# ps.net
KiCad netlist of a schematic drawn in EAGLE
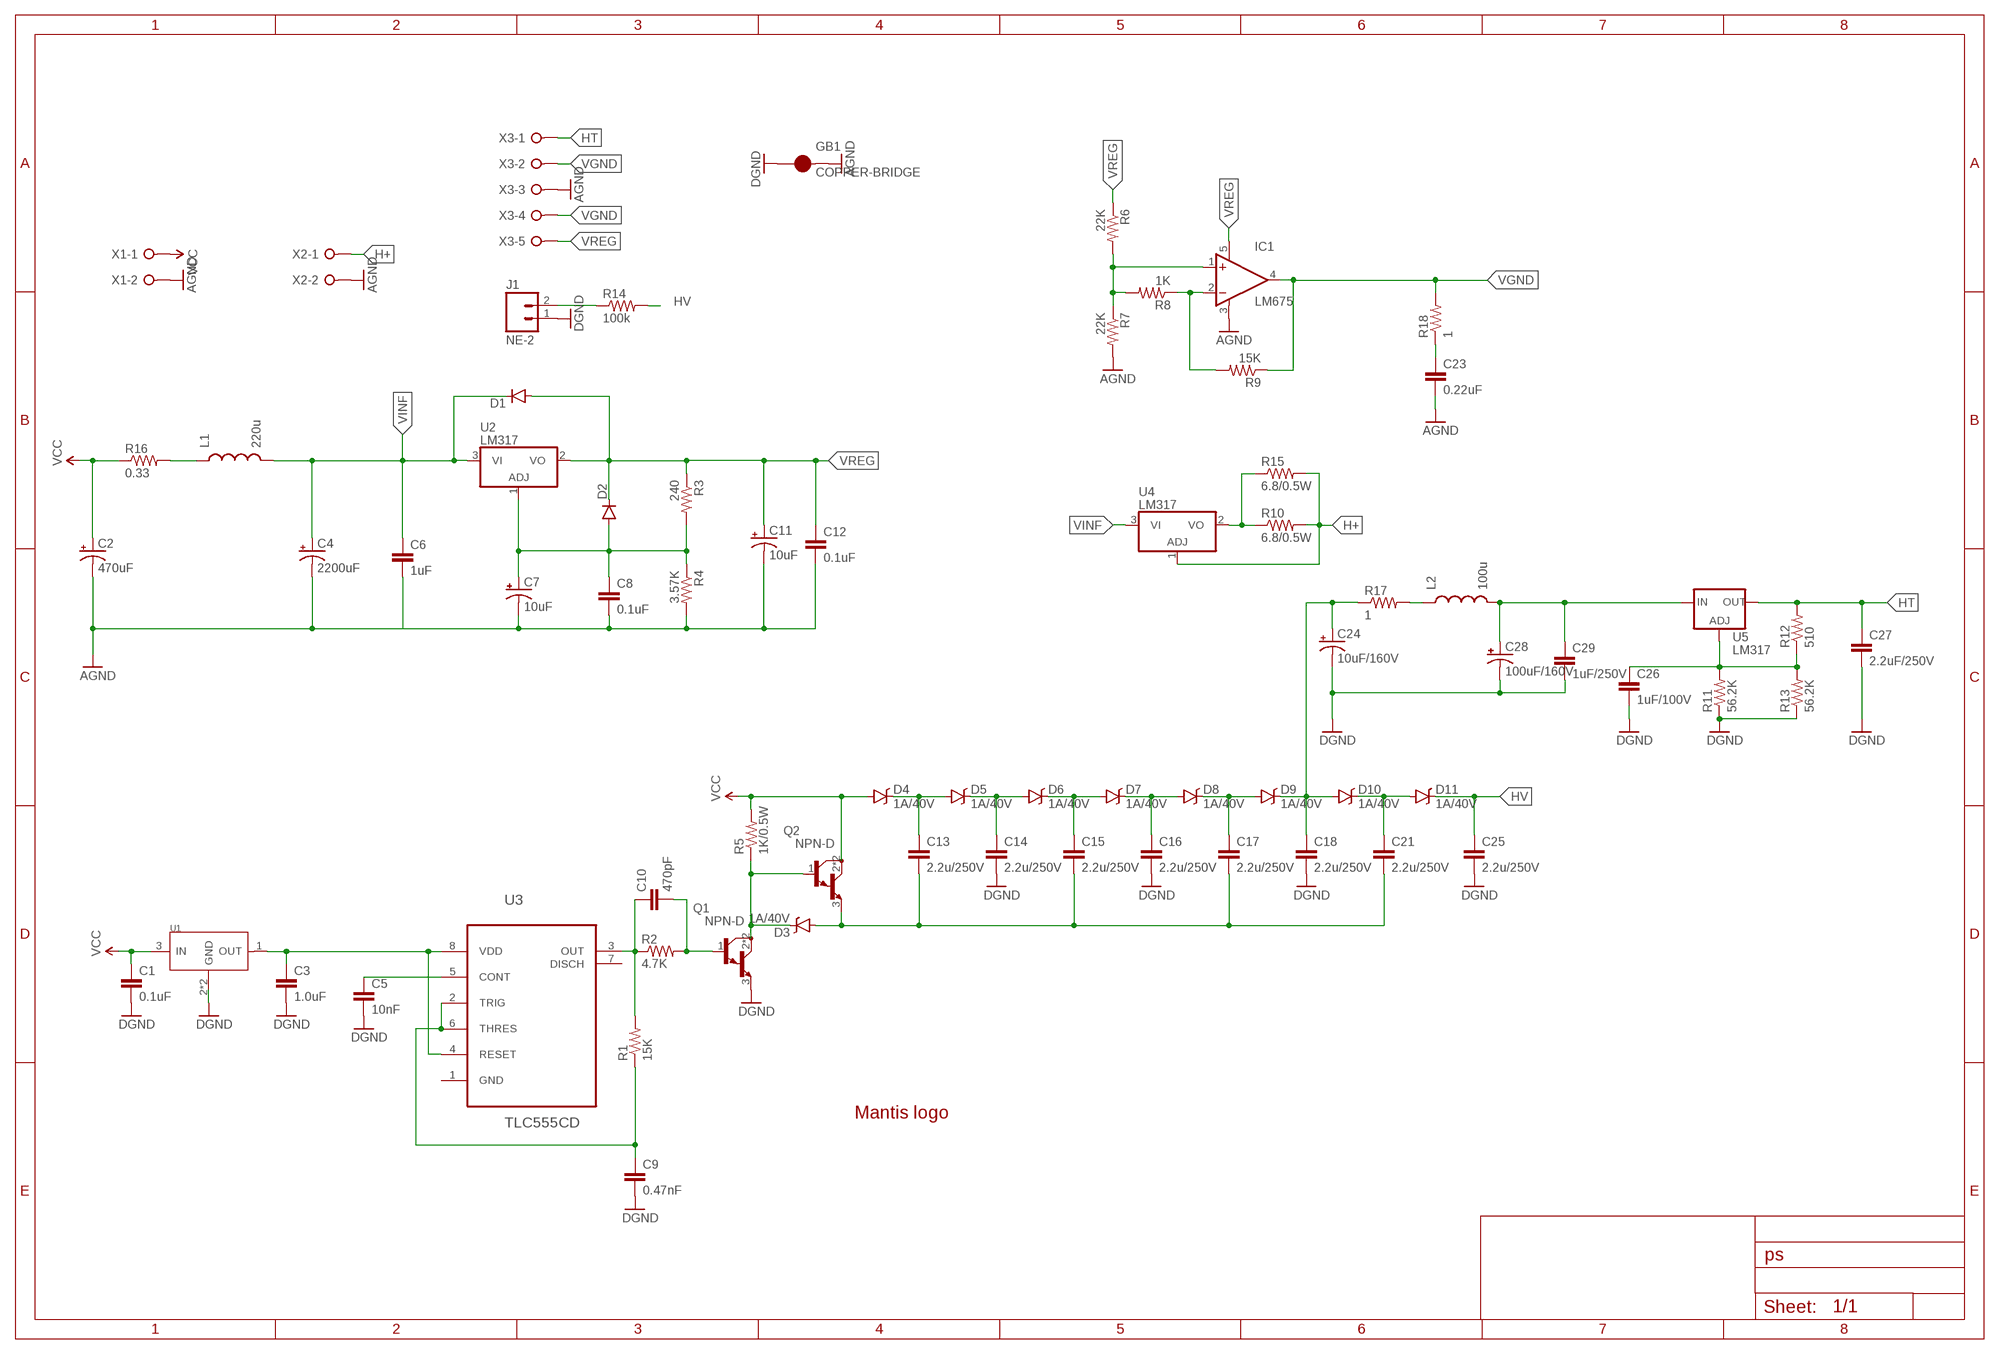
[diagram p0: schematic, sheet 1]

(export (version "E")
  (design (tool "Eeschema 10.0.6"))
  (components
    (comp (ref "C1")
      (value "0.1uF")
      (footprint "eagle-import:0603-CAP")
      (libsource (lib "eagle-import") (part "0.1UF-25V(+80/-20%)(0603)"))
    )
    (comp (ref "C2")
      (value "470uF")
      (footprint "eagle-import:CPOL-RADIAL-1000UF-25V")
      (libsource (lib "eagle-import") (part "CAP_POLPTH4"))
    )
    (comp (ref "C3")
      (value "1.0uF")
      (footprint "eagle-import:0805-CAP")
      (libsource (lib "eagle-import") (part "1.0UF-25V-+80/-20(0805){dblquote}"))
    )
    (comp (ref "C4")
      (value "2200uF")
      (footprint "eagle-import:CPOL-RADIAL-1000UF-63V")
      (libsource (lib "eagle-import") (part "CAP_POLPTH3"))
    )
    (comp (ref "C5")
      (value "10nF")
      (footprint "eagle-import:0603-CAP")
      (libsource (lib "eagle-import") (part "10NF/10000PF-50V-10%(0603)"))
    )
    (comp (ref "C6")
      (value "1uF")
      (footprint "eagle-import:0805-CAP")
      (libsource (lib "eagle-import") (part "1UF-25V-10%(0805){dblquote}"))
    )
    (comp (ref "C7")
      (value "10uF")
      (footprint "eagle-import:PANASONIC_C")
      (libsource (lib "eagle-import") (part "CAP_POLC"))
    )
    (comp (ref "C8")
      (value "0.1uF")
      (footprint "eagle-import:0603-CAP")
      (libsource (lib "eagle-import") (part "0.1UF-25V-5%(0603)"))
    )
    (comp (ref "C9")
      (value "0.47nF")
      (footprint "eagle-import:0603-CAP")
      (libsource (lib "eagle-import") (part "4.7NF-50V-10%(0603)"))
    )
    (comp (ref "C10")
      (value "470pF")
      (footprint "eagle-import:0603-CAP")
      (libsource (lib "eagle-import") (part "470PF-50V-5%(0603)SMD"))
    )
    (comp (ref "C11")
      (value "10uF")
      (footprint "eagle-import:PANASONIC_C")
      (libsource (lib "eagle-import") (part "CAP_POLC"))
    )
    (comp (ref "C12")
      (value "0.1uF")
      (footprint "eagle-import:0603-CAP")
      (libsource (lib "eagle-import") (part "0.1UF-25V-5%(0603)"))
    )
    (comp (ref "C13")
      (value "2.2u/250V")
      (footprint "eagle-import:C2220K")
      (libsource (lib "eagle-import") (part "C-EUC2220K"))
    )
    (comp (ref "C14")
      (value "2.2u/250V")
      (footprint "eagle-import:C2220K")
      (libsource (lib "eagle-import") (part "C-EUC2220K"))
    )
    (comp (ref "C15")
      (value "2.2u/250V")
      (footprint "eagle-import:C2220K")
      (libsource (lib "eagle-import") (part "C-EUC2220K"))
    )
    (comp (ref "C16")
      (value "2.2u/250V")
      (footprint "eagle-import:C2220K")
      (libsource (lib "eagle-import") (part "C-EUC2220K"))
    )
    (comp (ref "C17")
      (value "2.2u/250V")
      (footprint "eagle-import:C2220K")
      (libsource (lib "eagle-import") (part "C-EUC2220K"))
    )
    (comp (ref "C18")
      (value "2.2u/250V")
      (footprint "eagle-import:C2220K")
      (libsource (lib "eagle-import") (part "C-EUC2220K"))
    )
    (comp (ref "C21")
      (value "2.2u/250V")
      (footprint "eagle-import:C2220K")
      (libsource (lib "eagle-import") (part "C-EUC2220K"))
    )
    (comp (ref "C23")
      (value "0.22uF")
      (footprint "eagle-import:0603-CAP")
      (libsource (lib "eagle-import") (part "0.22UF-25V-10%(0603)"))
    )
    (comp (ref "C24")
      (value "10uF/160V")
      (footprint "eagle-import:CPOL-RADIAL-1000UF-25V")
      (libsource (lib "eagle-import") (part "CAP_POLPTH4"))
    )
    (comp (ref "C25")
      (value "2.2u/250V")
      (footprint "eagle-import:C2220K")
      (libsource (lib "eagle-import") (part "C-EUC2220K"))
    )
    (comp (ref "C26")
      (value "1uF/100V")
      (footprint "eagle-import:1210")
      (libsource (lib "eagle-import") (part "CAP1210"))
    )
    (comp (ref "C27")
      (value "2.2uF/250V")
      (footprint "eagle-import:C2220K")
      (libsource (lib "eagle-import") (part "C-EUC2220K"))
    )
    (comp (ref "C28")
      (value "100uF/160V")
      (footprint "eagle-import:CPOL-RADIAL-1000UF-25V")
      (libsource (lib "eagle-import") (part "CAP_POLPTH4"))
    )
    (comp (ref "C29")
      (value "1uF/250V")
      (footprint "eagle-import:C2220K")
      (libsource (lib "eagle-import") (part "C-EUC2220K"))
    )
    (comp (ref "D1")
      (value "DIODESOD123")
      (footprint "eagle-import:SOD-123")
      (libsource (lib "eagle-import") (part "DIODESOD123"))
    )
    (comp (ref "D2")
      (value "DIODESOD123")
      (footprint "eagle-import:SOD-123")
      (libsource (lib "eagle-import") (part "DIODESOD123"))
    )
    (comp (ref "D3")
      (value "1A/40V")
      (footprint "eagle-import:SMA-DIODE")
      (libsource (lib "eagle-import") (part "DIODE-SCHOTTKY-B340A"))
    )
    (comp (ref "D4")
      (value "1A/40V")
      (footprint "eagle-import:SMA-DIODE")
      (libsource (lib "eagle-import") (part "DIODE-SCHOTTKY-B340A"))
    )
    (comp (ref "D5")
      (value "1A/40V")
      (footprint "eagle-import:SMA-DIODE")
      (libsource (lib "eagle-import") (part "DIODE-SCHOTTKY-B340A"))
    )
    (comp (ref "D6")
      (value "1A/40V")
      (footprint "eagle-import:SMA-DIODE")
      (libsource (lib "eagle-import") (part "DIODE-SCHOTTKY-B340A"))
    )
    (comp (ref "D7")
      (value "1A/40V")
      (footprint "eagle-import:SMA-DIODE")
      (libsource (lib "eagle-import") (part "DIODE-SCHOTTKY-B340A"))
    )
    (comp (ref "D8")
      (value "1A/40V")
      (footprint "eagle-import:SMA-DIODE")
      (libsource (lib "eagle-import") (part "DIODE-SCHOTTKY-B340A"))
    )
    (comp (ref "D9")
      (value "1A/40V")
      (footprint "eagle-import:SMA-DIODE")
      (libsource (lib "eagle-import") (part "DIODE-SCHOTTKY-B340A"))
    )
    (comp (ref "D10")
      (value "1A/40V")
      (footprint "eagle-import:SMA-DIODE")
      (libsource (lib "eagle-import") (part "DIODE-SCHOTTKY-B340A"))
    )
    (comp (ref "D11")
      (value "1A/40V")
      (footprint "eagle-import:SMA-DIODE")
      (libsource (lib "eagle-import") (part "DIODE-SCHOTTKY-B340A"))
    )
    (comp (ref "GB1")
      (value "COPPER-BRIDGE")
      (footprint "eagle-import:COPPER-BRIDGE")
      (libsource (lib "eagle-import") (part "COPPER-BRIDGE"))
    )
    (comp (ref "IC1")
      (value "LM675")
      (footprint "eagle-import:TO220-5")
      (libsource (lib "eagle-import") (part "LM675"))
    )
    (comp (ref "J1")
      (value "NE-2")
      (footprint "eagle-import:1X02")
      (libsource (lib "eagle-import") (part "M02PTH"))
    )
    (comp (ref "L1")
      (value "220u")
      (footprint "eagle-import:NR10050T-PTH-ADD")
      (libsource (lib "eagle-import") (part "INDUCTORNR10050T-PTH-ADD"))
    )
    (comp (ref "L2")
      (value "100u")
      (footprint "eagle-import:1210")
      (libsource (lib "eagle-import") (part "INDUCTOR1210"))
    )
    (comp (ref "LOGO1")
      (value "LOGO-MANTIS")
      (footprint "eagle-import:LOGO-MANTIS")
      (libsource (lib "eagle-import") (part "LOGO-MANTIS"))
    )
    (comp (ref "Q1")
      (value "NPN-D")
      (footprint "eagle-import:SOT223")
      (libsource (lib "eagle-import") (part "NPN-D"))
    )
    (comp (ref "Q2")
      (value "NPN-D")
      (footprint "eagle-import:SOT223")
      (libsource (lib "eagle-import") (part "NPN-D"))
    )
    (comp (ref "R1")
      (value "15K")
      (footprint "eagle-import:0603-RES")
      (libsource (lib "eagle-import") (part "15KOHM1/10W1%(0603)0603"))
    )
    (comp (ref "R2")
      (value "4.7K")
      (footprint "eagle-import:0603-RES")
      (libsource (lib "eagle-import") (part "10KOHM-1/10W-1%(0603)0603"))
    )
    (comp (ref "R3")
      (value "240")
      (footprint "eagle-import:AXIAL-0.4")
      (libsource (lib "eagle-import") (part "RESISTORPTH-1/4W"))
    )
    (comp (ref "R4")
      (value "3.57K")
      (footprint "eagle-import:AXIAL-0.4")
      (libsource (lib "eagle-import") (part "RESISTORPTH-1/4W"))
    )
    (comp (ref "R5")
      (value "1K/0.5W")
      (footprint "eagle-import:R1210W")
      (libsource (lib "eagle-import") (part "R-US_R1210W"))
    )
    (comp (ref "R6")
      (value "22K")
      (footprint "eagle-import:AXIAL-0.4")
      (libsource (lib "eagle-import") (part "RESISTORPTH-1/4W"))
    )
    (comp (ref "R7")
      (value "22K")
      (footprint "eagle-import:AXIAL-0.4")
      (libsource (lib "eagle-import") (part "RESISTORPTH-1/4W"))
    )
    (comp (ref "R8")
      (value "1K")
      (footprint "eagle-import:AXIAL-0.4")
      (libsource (lib "eagle-import") (part "RESISTORPTH-1/4W"))
    )
    (comp (ref "R9")
      (value "15K")
      (footprint "eagle-import:AXIAL-0.4")
      (libsource (lib "eagle-import") (part "RESISTORPTH-1/4W"))
    )
    (comp (ref "R10")
      (value "6.8/0.5W")
      (footprint "eagle-import:AXIAL-0.5")
      (libsource (lib "eagle-import") (part "RESISTORPTH-1/2W"))
    )
    (comp (ref "R11")
      (value "56.2K")
      (footprint "eagle-import:AXIAL-0.4")
      (libsource (lib "eagle-import") (part "RESISTORPTH-1/4W"))
    )
    (comp (ref "R12")
      (value "510")
      (footprint "eagle-import:AXIAL-0.4")
      (libsource (lib "eagle-import") (part "RESISTORPTH-1/4W"))
    )
    (comp (ref "R13")
      (value "56.2K")
      (footprint "eagle-import:AXIAL-0.4")
      (libsource (lib "eagle-import") (part "RESISTORPTH-1/4W"))
    )
    (comp (ref "R14")
      (value "100k")
      (footprint "eagle-import:0603-RES")
      (libsource (lib "eagle-import") (part "100KOHM-1/10W-1%(0603)"))
    )
    (comp (ref "R15")
      (value "6.8/0.5W")
      (footprint "eagle-import:AXIAL-0.5")
      (libsource (lib "eagle-import") (part "RESISTORPTH-1/2W"))
    )
    (comp (ref "R16")
      (value "0.33")
      (footprint "eagle-import:AXIAL-0.4")
      (libsource (lib "eagle-import") (part "RESISTORPTH-1/4W"))
    )
    (comp (ref "R17")
      (value "1")
      (footprint "eagle-import:AXIAL-0.1")
      (libsource (lib "eagle-import") (part "RESISTORPTH-1/4W-VERT"))
    )
    (comp (ref "R18")
      (value "1")
      (footprint "eagle-import:AXIAL-0.4")
      (libsource (lib "eagle-import") (part "RESISTORPTH-1/4W"))
    )
    (comp (ref "U1")
      (value "L78L12ACUTR")
      (footprint "eagle-import:SOT-89")
      (libsource (lib "eagle-import") (part "L78L12ACUTR"))
    )
    (comp (ref "U2")
      (value "LM317")
      (footprint "eagle-import:TO220BV")
      (libsource (lib "eagle-import") (part "LM317"))
    )
    (comp (ref "U3")
      (value "TLC555CD")
      (footprint "eagle-import:SOIC127P600X175-8N")
      (libsource (lib "eagle-import") (part "TLC555CD"))
    )
    (comp (ref "U4")
      (value "LM317")
      (footprint "eagle-import:TO220BV")
      (libsource (lib "eagle-import") (part "LM317"))
    )
    (comp (ref "U5")
      (value "LM317")
      (footprint "eagle-import:V-REG_DPACK")
      (libsource (lib "eagle-import") (part "V_REG_317DPACK"))
    )
    (comp (ref "X1")
      (value "W237-02P")
      (footprint "eagle-import:W237-132")
      (libsource (lib "eagle-import") (part "W237-02P"))
    )
    (comp (ref "X2")
      (value "W237-02P")
      (footprint "eagle-import:W237-132")
      (libsource (lib "eagle-import") (part "W237-02P"))
    )
    (comp (ref "X3")
      (value "W237-05P")
      (footprint "eagle-import:W237-5P")
      (libsource (lib "eagle-import") (part "W237-05P"))
    )
  )
  (nets
    (net (code "1") (name "AGND") (class "Default")
      (node (ref "C11") (pin "-") (pinfunction "-_-") (pintype "passive"))
      (node (ref "C12") (pin "2") (pinfunction "2_2") (pintype "passive"))
      (node (ref "C2") (pin "-") (pinfunction "-_-") (pintype "passive"))
      (node (ref "C23") (pin "2") (pinfunction "2_2") (pintype "passive"))
      (node (ref "C4") (pin "2") (pinfunction "-_2") (pintype "passive"))
      (node (ref "C6") (pin "2") (pinfunction "2_2") (pintype "passive"))
      (node (ref "C7") (pin "-") (pinfunction "-_-") (pintype "passive"))
      (node (ref "C8") (pin "2") (pinfunction "2_2") (pintype "passive"))
      (node (ref "GB1") (pin "P$2.1") (pinfunction "2_P$2.1") (pintype "passive"))
      (node (ref "GB1") (pin "P$2.2") (pinfunction "2_P$2.2") (pintype "passive"))
      (node (ref "IC1") (pin "3") (pinfunction "V-_3") (pintype "power_in"))
      (node (ref "R4") (pin "P$2") (pinfunction "2_P$2") (pintype "passive"))
      (node (ref "R7") (pin "P$2") (pinfunction "2_P$2") (pintype "passive"))
      (node (ref "X1") (pin "2") (pinfunction "KL_2") (pintype "passive"))
      (node (ref "X2") (pin "2") (pinfunction "KL_2") (pintype "passive"))
      (node (ref "X3") (pin "3") (pinfunction "KL_3") (pintype "passive"))
    )
    (net (code "2") (name "DGND") (class "Default")
      (node (ref "C1") (pin "2") (pinfunction "2_2") (pintype "passive"))
      (node (ref "C14") (pin "2") (pinfunction "2_2") (pintype "passive"))
      (node (ref "C16") (pin "2") (pinfunction "2_2") (pintype "passive"))
      (node (ref "C18") (pin "2") (pinfunction "2_2") (pintype "passive"))
      (node (ref "C24") (pin "-") (pinfunction "-_-") (pintype "passive"))
      (node (ref "C25") (pin "2") (pinfunction "2_2") (pintype "passive"))
      (node (ref "C26") (pin "2") (pinfunction "2_2") (pintype "passive"))
      (node (ref "C27") (pin "2") (pinfunction "2_2") (pintype "passive"))
      (node (ref "C28") (pin "-") (pinfunction "-_-") (pintype "passive"))
      (node (ref "C29") (pin "2") (pinfunction "2_2") (pintype "passive"))
      (node (ref "C3") (pin "2") (pinfunction "2_2") (pintype "passive"))
      (node (ref "C5") (pin "2") (pinfunction "2_2") (pintype "passive"))
      (node (ref "C9") (pin "2") (pinfunction "2_2") (pintype "passive"))
      (node (ref "GB1") (pin "P$1.1") (pinfunction "1_P$1.1") (pintype "passive"))
      (node (ref "GB1") (pin "P$1.2") (pinfunction "1_P$1.2") (pintype "passive"))
      (node (ref "J1") (pin "1") (pinfunction "1_1") (pintype "passive"))
      (node (ref "Q1") (pin "3") (pinfunction "E_3") (pintype "passive"))
      (node (ref "R11") (pin "P$1") (pinfunction "1_P$1") (pintype "passive"))
      (node (ref "R13") (pin "P$1") (pinfunction "1_P$1") (pintype "passive"))
      (node (ref "U1") (pin "2") (pinfunction "GND_2") (pintype "bidirectional"))
      (node (ref "U1") (pin "PAD") (pinfunction "GND_PAD") (pintype "bidirectional"))
    )
    (net (code "3") (name "H+") (class "Default")
      (node (ref "R10") (pin "P$2") (pinfunction "2_P$2") (pintype "passive"))
      (node (ref "R15") (pin "P$2") (pinfunction "2_P$2") (pintype "passive"))
      (node (ref "U4") (pin "1") (pinfunction "ADJ_1") (pintype "input"))
      (node (ref "X2") (pin "1") (pinfunction "KL_1") (pintype "passive"))
    )
    (net (code "4") (name "HT") (class "Default")
      (node (ref "C27") (pin "1") (pinfunction "1_1") (pintype "passive"))
      (node (ref "R12") (pin "P$2") (pinfunction "2_P$2") (pintype "passive"))
      (node (ref "U5") (pin "4") (pinfunction "OUT_4") (pintype "output"))
      (node (ref "X3") (pin "1") (pinfunction "KL_1") (pintype "passive"))
    )
    (net (code "5") (name "HV") (class "Default")
      (node (ref "C25") (pin "1") (pinfunction "1_1") (pintype "passive"))
      (node (ref "D11") (pin "C") (pinfunction "C_C") (pintype "passive"))
      (node (ref "R14") (pin "2") (pinfunction "2_2") (pintype "passive"))
    )
    (net (code "6") (name "Net-(C13-Pad1)") (class "Default")
      (node (ref "C13") (pin "1") (pinfunction "1_1") (pintype "passive"))
      (node (ref "D4") (pin "C") (pinfunction "C_C") (pintype "passive"))
      (node (ref "D5") (pin "A") (pinfunction "A_A") (pintype "passive"))
    )
    (net (code "7") (name "Net-(C14-Pad1)") (class "Default")
      (node (ref "C14") (pin "1") (pinfunction "1_1") (pintype "passive"))
      (node (ref "D5") (pin "C") (pinfunction "C_C") (pintype "passive"))
      (node (ref "D6") (pin "A") (pinfunction "A_A") (pintype "passive"))
    )
    (net (code "8") (name "Net-(C15-Pad1)") (class "Default")
      (node (ref "C15") (pin "1") (pinfunction "1_1") (pintype "passive"))
      (node (ref "D6") (pin "C") (pinfunction "C_C") (pintype "passive"))
      (node (ref "D7") (pin "A") (pinfunction "A_A") (pintype "passive"))
    )
    (net (code "9") (name "Net-(C16-Pad1)") (class "Default")
      (node (ref "C16") (pin "1") (pinfunction "1_1") (pintype "passive"))
      (node (ref "D7") (pin "C") (pinfunction "C_C") (pintype "passive"))
      (node (ref "D8") (pin "A") (pinfunction "A_A") (pintype "passive"))
    )
    (net (code "10") (name "Net-(C17-Pad1)") (class "Default")
      (node (ref "C17") (pin "1") (pinfunction "1_1") (pintype "passive"))
      (node (ref "D8") (pin "C") (pinfunction "C_C") (pintype "passive"))
      (node (ref "D9") (pin "A") (pinfunction "A_A") (pintype "passive"))
    )
    (net (code "11") (name "Net-(C21-Pad1)") (class "Default")
      (node (ref "C21") (pin "1") (pinfunction "1_1") (pintype "passive"))
      (node (ref "D10") (pin "C") (pinfunction "C_C") (pintype "passive"))
      (node (ref "D11") (pin "A") (pinfunction "A_A") (pintype "passive"))
    )
    (net (code "12") (name "Net-(IC1-+IN)") (class "Default")
      (node (ref "IC1") (pin "1") (pinfunction "+IN_1") (pintype "input"))
      (node (ref "R6") (pin "P$2") (pinfunction "2_P$2") (pintype "passive"))
      (node (ref "R7") (pin "P$1") (pinfunction "1_P$1") (pintype "passive"))
      (node (ref "R8") (pin "P$2") (pinfunction "2_P$2") (pintype "passive"))
    )
    (net (code "13") (name "Net-(IC1--IN)") (class "Default")
      (node (ref "IC1") (pin "2") (pinfunction "-IN_2") (pintype "input"))
      (node (ref "R8") (pin "P$1") (pinfunction "1_P$1") (pintype "passive"))
      (node (ref "R9") (pin "P$2") (pinfunction "2_P$2") (pintype "passive"))
    )
    (net (code "14") (name "Net-(J1-Pad2)") (class "Default")
      (node (ref "J1") (pin "2") (pinfunction "2_2") (pintype "passive"))
      (node (ref "R14") (pin "1") (pinfunction "1_1") (pintype "passive"))
    )
    (net (code "15") (name "Net-(Q1-B)") (class "Default")
      (node (ref "C10") (pin "2") (pinfunction "2_2") (pintype "passive"))
      (node (ref "Q1") (pin "1") (pinfunction "B_1") (pintype "passive"))
      (node (ref "R2") (pin "2") (pinfunction "2_2") (pintype "passive"))
    )
    (net (code "16") (name "Net-(Q2-B)") (class "Default")
      (node (ref "D3") (pin "C") (pinfunction "C_C") (pintype "passive"))
      (node (ref "Q1") (pin "2") (pinfunction "C_2") (pintype "passive"))
      (node (ref "Q1") (pin "4") (pinfunction "C_4") (pintype "passive"))
      (node (ref "Q2") (pin "1") (pinfunction "B_1") (pintype "passive"))
      (node (ref "R5") (pin "1") (pinfunction "1_1") (pintype "passive"))
    )
    (net (code "17") (name "Net-(Q2-E)") (class "Default")
      (node (ref "C13") (pin "2") (pinfunction "2_2") (pintype "passive"))
      (node (ref "C15") (pin "2") (pinfunction "2_2") (pintype "passive"))
      (node (ref "C17") (pin "2") (pinfunction "2_2") (pintype "passive"))
      (node (ref "C21") (pin "2") (pinfunction "2_2") (pintype "passive"))
      (node (ref "D3") (pin "A") (pinfunction "A_A") (pintype "passive"))
      (node (ref "Q2") (pin "3") (pinfunction "E_3") (pintype "passive"))
    )
    (net (code "18") (name "Net-(R3-2)") (class "Default")
      (node (ref "C7") (pin "+") (pinfunction "+_+") (pintype "passive"))
      (node (ref "C8") (pin "1") (pinfunction "1_1") (pintype "passive"))
      (node (ref "D2") (pin "A") (pinfunction "A_A") (pintype "passive"))
      (node (ref "R3") (pin "P$2") (pinfunction "2_P$2") (pintype "passive"))
      (node (ref "R4") (pin "P$1") (pinfunction "1_P$1") (pintype "passive"))
      (node (ref "U2") (pin "1") (pinfunction "ADJ_1") (pintype "input"))
    )
    (net (code "19") (name "Net-(R10-1)") (class "Default")
      (node (ref "R10") (pin "P$1") (pinfunction "1_P$1") (pintype "passive"))
      (node (ref "R15") (pin "P$1") (pinfunction "1_P$1") (pintype "passive"))
      (node (ref "U4") (pin "2") (pinfunction "VO_2") (pintype "passive"))
    )
    (net (code "20") (name "Net-(R11-2)") (class "Default")
      (node (ref "C26") (pin "1") (pinfunction "1_1") (pintype "passive"))
      (node (ref "R11") (pin "P$2") (pinfunction "2_P$2") (pintype "passive"))
      (node (ref "R12") (pin "P$1") (pinfunction "1_P$1") (pintype "passive"))
      (node (ref "R13") (pin "P$2") (pinfunction "2_P$2") (pintype "passive"))
      (node (ref "U5") (pin "1") (pinfunction "ADJ_1") (pintype "input"))
    )
    (net (code "21") (name "Net-(R16-2)") (class "Default")
      (node (ref "L1") (pin "P$1") (pinfunction "1_P$1") (pintype "passive"))
      (node (ref "L1") (pin "P$1.1") (pinfunction "1_P$1.1") (pintype "passive"))
      (node (ref "R16") (pin "P$2") (pinfunction "2_P$2") (pintype "passive"))
    )
    (net (code "22") (name "Net-(R17-1)") (class "Default")
      (node (ref "C18") (pin "1") (pinfunction "1_1") (pintype "passive"))
      (node (ref "C24") (pin "+") (pinfunction "+_+") (pintype "passive"))
      (node (ref "D10") (pin "A") (pinfunction "A_A") (pintype "passive"))
      (node (ref "D9") (pin "C") (pinfunction "C_C") (pintype "passive"))
      (node (ref "R17") (pin "P$1") (pinfunction "1_P$1") (pintype "passive"))
    )
    (net (code "23") (name "Net-(R17-2)") (class "Default")
      (node (ref "L2") (pin "1") (pinfunction "1_1") (pintype "passive"))
      (node (ref "R17") (pin "P$2") (pinfunction "2_P$2") (pintype "passive"))
    )
    (net (code "24") (name "Net-(R18-1)") (class "Default")
      (node (ref "C23") (pin "1") (pinfunction "1_1") (pintype "passive"))
      (node (ref "R18") (pin "P$1") (pinfunction "1_P$1") (pintype "passive"))
    )
    (net (code "25") (name "Net-(U1-OUT)") (class "Default")
      (node (ref "C3") (pin "1") (pinfunction "1_1") (pintype "passive"))
      (node (ref "U1") (pin "1") (pinfunction "OUT_1") (pintype "bidirectional"))
      (node (ref "U3") (pin "4") (pinfunction "RESET_4") (pintype "input"))
      (node (ref "U3") (pin "8") (pinfunction "VDD_8") (pintype "power_in"))
    )
    (net (code "26") (name "Net-(U3-CONT)") (class "Default")
      (node (ref "C5") (pin "1") (pinfunction "1_1") (pintype "passive"))
      (node (ref "U3") (pin "5") (pinfunction "CONT_5") (pintype "input"))
    )
    (net (code "27") (name "Net-(U3-OUT)") (class "Default")
      (node (ref "C10") (pin "1") (pinfunction "1_1") (pintype "passive"))
      (node (ref "R1") (pin "2") (pinfunction "2_2") (pintype "passive"))
      (node (ref "R2") (pin "1") (pinfunction "1_1") (pintype "passive"))
      (node (ref "U3") (pin "3") (pinfunction "OUT_3") (pintype "output"))
    )
    (net (code "28") (name "Net-(U3-THRES)") (class "Default")
      (node (ref "C9") (pin "1") (pinfunction "1_1") (pintype "passive"))
      (node (ref "R1") (pin "1") (pinfunction "1_1") (pintype "passive"))
      (node (ref "U3") (pin "2") (pinfunction "TRIG_2") (pintype "input"))
      (node (ref "U3") (pin "6") (pinfunction "THRES_6") (pintype "input"))
    )
    (net (code "29") (name "Net-(U5-IN)") (class "Default")
      (node (ref "C28") (pin "+") (pinfunction "+_+") (pintype "passive"))
      (node (ref "C29") (pin "1") (pinfunction "1_1") (pintype "passive"))
      (node (ref "L2") (pin "2") (pinfunction "2_2") (pintype "passive"))
      (node (ref "U5") (pin "3") (pinfunction "IN_3") (pintype "input"))
    )
    (net (code "30") (name "VCC") (class "Default")
      (node (ref "C1") (pin "1") (pinfunction "1_1") (pintype "passive"))
      (node (ref "C2") (pin "+") (pinfunction "+_+") (pintype "passive"))
      (node (ref "D4") (pin "A") (pinfunction "A_A") (pintype "passive"))
      (node (ref "Q2") (pin "2") (pinfunction "C_2") (pintype "passive"))
      (node (ref "Q2") (pin "4") (pinfunction "C_4") (pintype "passive"))
      (node (ref "R16") (pin "P$1") (pinfunction "1_P$1") (pintype "passive"))
      (node (ref "R5") (pin "2") (pinfunction "2_2") (pintype "passive"))
      (node (ref "U1") (pin "3") (pinfunction "IN_3") (pintype "bidirectional"))
      (node (ref "X1") (pin "1") (pinfunction "KL_1") (pintype "passive"))
    )
    (net (code "31") (name "VGND") (class "Default")
      (node (ref "IC1") (pin "4") (pinfunction "OUT_4") (pintype "output"))
      (node (ref "R18") (pin "P$2") (pinfunction "2_P$2") (pintype "passive"))
      (node (ref "R9") (pin "P$1") (pinfunction "1_P$1") (pintype "passive"))
      (node (ref "X3") (pin "2") (pinfunction "KL_2") (pintype "passive"))
      (node (ref "X3") (pin "4") (pinfunction "KL_4") (pintype "passive"))
    )
    (net (code "32") (name "VINF") (class "Default")
      (node (ref "C4") (pin "1") (pinfunction "+_1") (pintype "passive"))
      (node (ref "C6") (pin "1") (pinfunction "1_1") (pintype "passive"))
      (node (ref "D1") (pin "C") (pinfunction "C_C") (pintype "passive"))
      (node (ref "L1") (pin "P$2") (pinfunction "2_P$2") (pintype "passive"))
      (node (ref "L1") (pin "P$2.1") (pinfunction "2_P$2.1") (pintype "passive"))
      (node (ref "U2") (pin "3") (pinfunction "VI_3") (pintype "input"))
      (node (ref "U4") (pin "3") (pinfunction "VI_3") (pintype "input"))
    )
    (net (code "33") (name "VREG") (class "Default")
      (node (ref "C11") (pin "+") (pinfunction "+_+") (pintype "passive"))
      (node (ref "C12") (pin "1") (pinfunction "1_1") (pintype "passive"))
      (node (ref "D1") (pin "A") (pinfunction "A_A") (pintype "passive"))
      (node (ref "D2") (pin "C") (pinfunction "C_C") (pintype "passive"))
      (node (ref "IC1") (pin "5") (pinfunction "V+_5") (pintype "power_in"))
      (node (ref "R3") (pin "P$1") (pinfunction "1_P$1") (pintype "passive"))
      (node (ref "R6") (pin "P$1") (pinfunction "1_P$1") (pintype "passive"))
      (node (ref "U2") (pin "2") (pinfunction "VO_2") (pintype "passive"))
      (node (ref "X3") (pin "5") (pinfunction "KL_5") (pintype "passive"))
    )
    (net (code "34") (name "unconnected-(U3-DISCH-Pad7)") (class "Default")
      (node (ref "U3") (pin "7") (pinfunction "DISCH_7") (pintype "output"))
    )
    (net (code "35") (name "unconnected-(U3-GND-Pad1)") (class "Default")
      (node (ref "U3") (pin "1") (pinfunction "GND_1") (pintype "passive"))
    )
  )
)
